# preamp.net
KiCad netlist of a schematic drawn in EAGLE
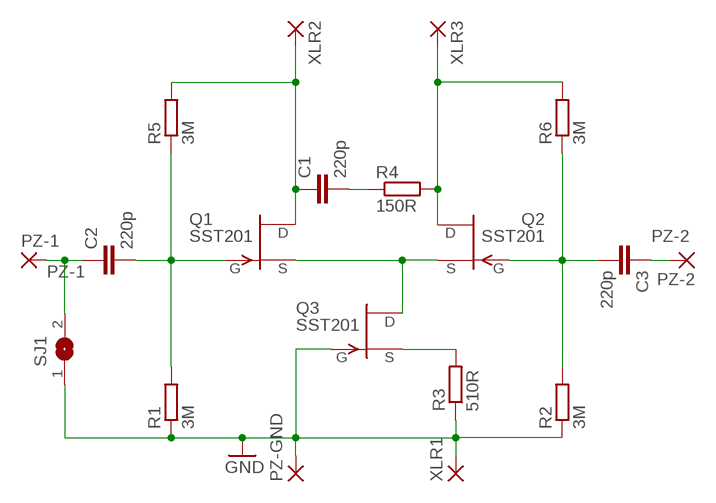
[diagram p0: schematic, sheet 1]

(export (version "E")
  (design (tool "Eeschema 10.0.6"))
  (components
    (comp (ref "C1")
      (value "220p")
      (footprint "eagle-import:C1206")
      (libsource (lib "eagle-import") (part "C-EUC1206"))
    )
    (comp (ref "C2")
      (value "220p")
      (footprint "eagle-import:C1206")
      (libsource (lib "eagle-import") (part "C-EUC1206"))
    )
    (comp (ref "C3")
      (value "220p")
      (footprint "eagle-import:C1206")
      (libsource (lib "eagle-import") (part "C-EUC1206"))
    )
    (comp (ref "PZ-1")
      (value "3,17/1,3")
      (footprint "eagle-import:3,17_1,3")
      (libsource (lib "eagle-import") (part "3,17/1,3"))
    )
    (comp (ref "PZ-2")
      (value "3,17/1,3")
      (footprint "eagle-import:3,17_1,3")
      (libsource (lib "eagle-import") (part "3,17/1,3"))
    )
    (comp (ref "PZ-GND")
      (value "3,17/1,3")
      (footprint "eagle-import:3,17_1,3")
      (libsource (lib "eagle-import") (part "3,17/1,3"))
    )
    (comp (ref "Q1")
      (value "SST201")
      (footprint "eagle-import:SOT23")
      (libsource (lib "eagle-import") (part "?20SST1"))
    )
    (comp (ref "Q2")
      (value "SST201")
      (footprint "eagle-import:SOT23")
      (libsource (lib "eagle-import") (part "?20SST1"))
    )
    (comp (ref "Q3")
      (value "SST201")
      (footprint "eagle-import:SOT23")
      (libsource (lib "eagle-import") (part "?20SST1"))
    )
    (comp (ref "R1")
      (value "3M")
      (footprint "eagle-import:R1206")
      (libsource (lib "eagle-import") (part "R-EU_R1206"))
    )
    (comp (ref "R2")
      (value "3M")
      (footprint "eagle-import:R1206")
      (libsource (lib "eagle-import") (part "R-EU_R1206"))
    )
    (comp (ref "R3")
      (value "510R")
      (footprint "eagle-import:R1206")
      (libsource (lib "eagle-import") (part "R-EU_R1206"))
    )
    (comp (ref "R4")
      (value "150R")
      (footprint "eagle-import:R1206")
      (libsource (lib "eagle-import") (part "R-EU_R1206"))
    )
    (comp (ref "R5")
      (value "3M")
      (footprint "eagle-import:R1206")
      (libsource (lib "eagle-import") (part "R-EU_R1206"))
    )
    (comp (ref "R6")
      (value "3M")
      (footprint "eagle-import:R1206")
      (libsource (lib "eagle-import") (part "R-EU_R1206"))
    )
    (comp (ref "SJ1") (value "SJ") (footprint "eagle-import:SJ") (libsource (lib "eagle-import") (part "SJ")))
    (comp (ref "XLR1")
      (value "3,17/1,3")
      (footprint "eagle-import:3,17_1,3")
      (libsource (lib "eagle-import") (part "3,17/1,3"))
    )
    (comp (ref "XLR2")
      (value "3,17/1,3")
      (footprint "eagle-import:3,17_1,3")
      (libsource (lib "eagle-import") (part "3,17/1,3"))
    )
    (comp (ref "XLR3")
      (value "3,17/1,3")
      (footprint "eagle-import:3,17_1,3")
      (libsource (lib "eagle-import") (part "3,17/1,3"))
    )
  )
  (nets
    (net (code "1") (name "/PZ-1") (class "Default")
      (node (ref "C2") (pin "1") (pinfunction "1_1") (pintype "passive"))
      (node (ref "PZ-1") (pin "1") (pinfunction "P_1") (pintype "passive"))
      (node (ref "SJ1") (pin "2") (pinfunction "2_2") (pintype "passive"))
    )
    (net (code "2") (name "/PZ-2") (class "Default")
      (node (ref "C3") (pin "1") (pinfunction "1_1") (pintype "passive"))
      (node (ref "PZ-2") (pin "1") (pinfunction "P_1") (pintype "passive"))
    )
    (net (code "3") (name "GND") (class "Default")
      (node (ref "PZ-GND") (pin "1") (pinfunction "P_1") (pintype "passive"))
      (node (ref "Q3") (pin "3") (pinfunction "G_3") (pintype "passive"))
      (node (ref "R1") (pin "1") (pinfunction "1_1") (pintype "passive"))
      (node (ref "R2") (pin "1") (pinfunction "1_1") (pintype "passive"))
      (node (ref "R3") (pin "1") (pinfunction "1_1") (pintype "passive"))
      (node (ref "SJ1") (pin "1") (pinfunction "1_1") (pintype "passive"))
      (node (ref "XLR1") (pin "1") (pinfunction "P_1") (pintype "passive"))
    )
    (net (code "4") (name "Net-(C1-Pad2)") (class "Default")
      (node (ref "C1") (pin "2") (pinfunction "2_2") (pintype "passive"))
      (node (ref "R4") (pin "1") (pinfunction "1_1") (pintype "passive"))
    )
    (net (code "5") (name "Net-(Q1-D)") (class "Default")
      (node (ref "C1") (pin "1") (pinfunction "1_1") (pintype "passive"))
      (node (ref "Q1") (pin "1") (pinfunction "D_1") (pintype "passive"))
      (node (ref "R5") (pin "2") (pinfunction "2_2") (pintype "passive"))
      (node (ref "XLR2") (pin "1") (pinfunction "P_1") (pintype "passive"))
    )
    (net (code "6") (name "Net-(Q1-G)") (class "Default")
      (node (ref "C2") (pin "2") (pinfunction "2_2") (pintype "passive"))
      (node (ref "Q1") (pin "3") (pinfunction "G_3") (pintype "passive"))
      (node (ref "R1") (pin "2") (pinfunction "2_2") (pintype "passive"))
      (node (ref "R5") (pin "1") (pinfunction "1_1") (pintype "passive"))
    )
    (net (code "7") (name "Net-(Q1-S)") (class "Default")
      (node (ref "Q1") (pin "2") (pinfunction "S_2") (pintype "passive"))
      (node (ref "Q2") (pin "2") (pinfunction "S_2") (pintype "passive"))
      (node (ref "Q3") (pin "1") (pinfunction "D_1") (pintype "passive"))
    )
    (net (code "8") (name "Net-(Q2-D)") (class "Default")
      (node (ref "Q2") (pin "1") (pinfunction "D_1") (pintype "passive"))
      (node (ref "R4") (pin "2") (pinfunction "2_2") (pintype "passive"))
      (node (ref "R6") (pin "2") (pinfunction "2_2") (pintype "passive"))
      (node (ref "XLR3") (pin "1") (pinfunction "P_1") (pintype "passive"))
    )
    (net (code "9") (name "Net-(Q2-G)") (class "Default")
      (node (ref "C3") (pin "2") (pinfunction "2_2") (pintype "passive"))
      (node (ref "Q2") (pin "3") (pinfunction "G_3") (pintype "passive"))
      (node (ref "R2") (pin "2") (pinfunction "2_2") (pintype "passive"))
      (node (ref "R6") (pin "1") (pinfunction "1_1") (pintype "passive"))
    )
    (net (code "10") (name "Net-(Q3-S)") (class "Default")
      (node (ref "Q3") (pin "2") (pinfunction "S_2") (pintype "passive"))
      (node (ref "R3") (pin "2") (pinfunction "2_2") (pintype "passive"))
    )
  )
)
